# Sensor2.net
KiCad netlist of a schematic drawn in EAGLE
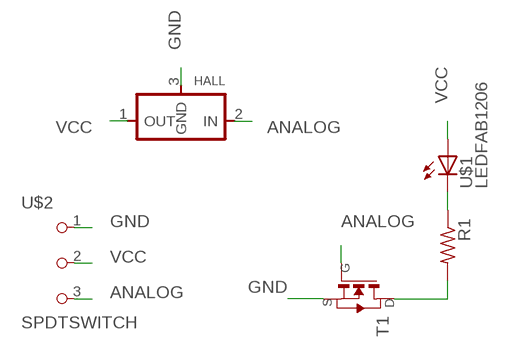
[diagram p0: schematic, sheet 1]

(export (version "E")
  (design (tool "Eeschema 10.0.6"))
  (components
    (comp (ref "HALL")
      (value "REGULATORSOT23")
      (footprint "eagle-import:SOT23")
      (libsource (lib "eagle-import") (part "REGULATORSOT23"))
    )
    (comp (ref "R1")
      (value "RES-US1206FAB")
      (footprint "eagle-import:R1206FAB")
      (libsource (lib "eagle-import") (part "RES-US1206FAB"))
    )
    (comp (ref "T1")
      (value "NMOSFETSOT23")
      (footprint "eagle-import:SOT-23")
      (libsource (lib "eagle-import") (part "NMOSFETSOT23"))
    )
    (comp (ref "U$1")
      (value "LEDFAB1206")
      (footprint "eagle-import:LED1206FAB")
      (libsource (lib "eagle-import") (part "LEDFAB1206"))
    )
    (comp (ref "U$2")
      (value "SPDTSWITCH")
      (footprint "eagle-import:SPDTSWITCH")
      (libsource (lib "eagle-import") (part "SPDTSWITCH"))
    )
  )
  (nets
    (net (code "1") (name "/ANALOG") (class "Default")
      (node (ref "HALL") (pin "2") (pinfunction "IN_2") (pintype "bidirectional"))
      (node (ref "T1") (pin "3") (pinfunction "G_3") (pintype "passive"))
      (node (ref "U$2") (pin "3") (pinfunction "3_3") (pintype "passive"))
    )
    (net (code "2") (name "/GND") (class "Default")
      (node (ref "HALL") (pin "3") (pinfunction "GND_3") (pintype "bidirectional"))
      (node (ref "T1") (pin "2") (pinfunction "S_2") (pintype "passive"))
      (node (ref "U$2") (pin "1") (pinfunction "1_1") (pintype "passive"))
    )
    (net (code "3") (name "/VCC") (class "Default")
      (node (ref "HALL") (pin "1") (pinfunction "OUT_1") (pintype "bidirectional"))
      (node (ref "U$1") (pin "1") (pinfunction "A_1") (pintype "passive"))
      (node (ref "U$2") (pin "2") (pinfunction "2_2") (pintype "passive"))
    )
    (net (code "4") (name "Net-(T1-D)") (class "Default")
      (node (ref "R1") (pin "2") (pinfunction "2_2") (pintype "passive"))
      (node (ref "T1") (pin "1") (pinfunction "D_1") (pintype "passive"))
    )
    (net (code "5") (name "Net-(U$1-C)") (class "Default")
      (node (ref "R1") (pin "1") (pinfunction "1_1") (pintype "passive"))
      (node (ref "U$1") (pin "2") (pinfunction "C_2") (pintype "passive"))
    )
  )
)
